# control-17.net
KiCad netlist of a schematic drawn in EAGLE
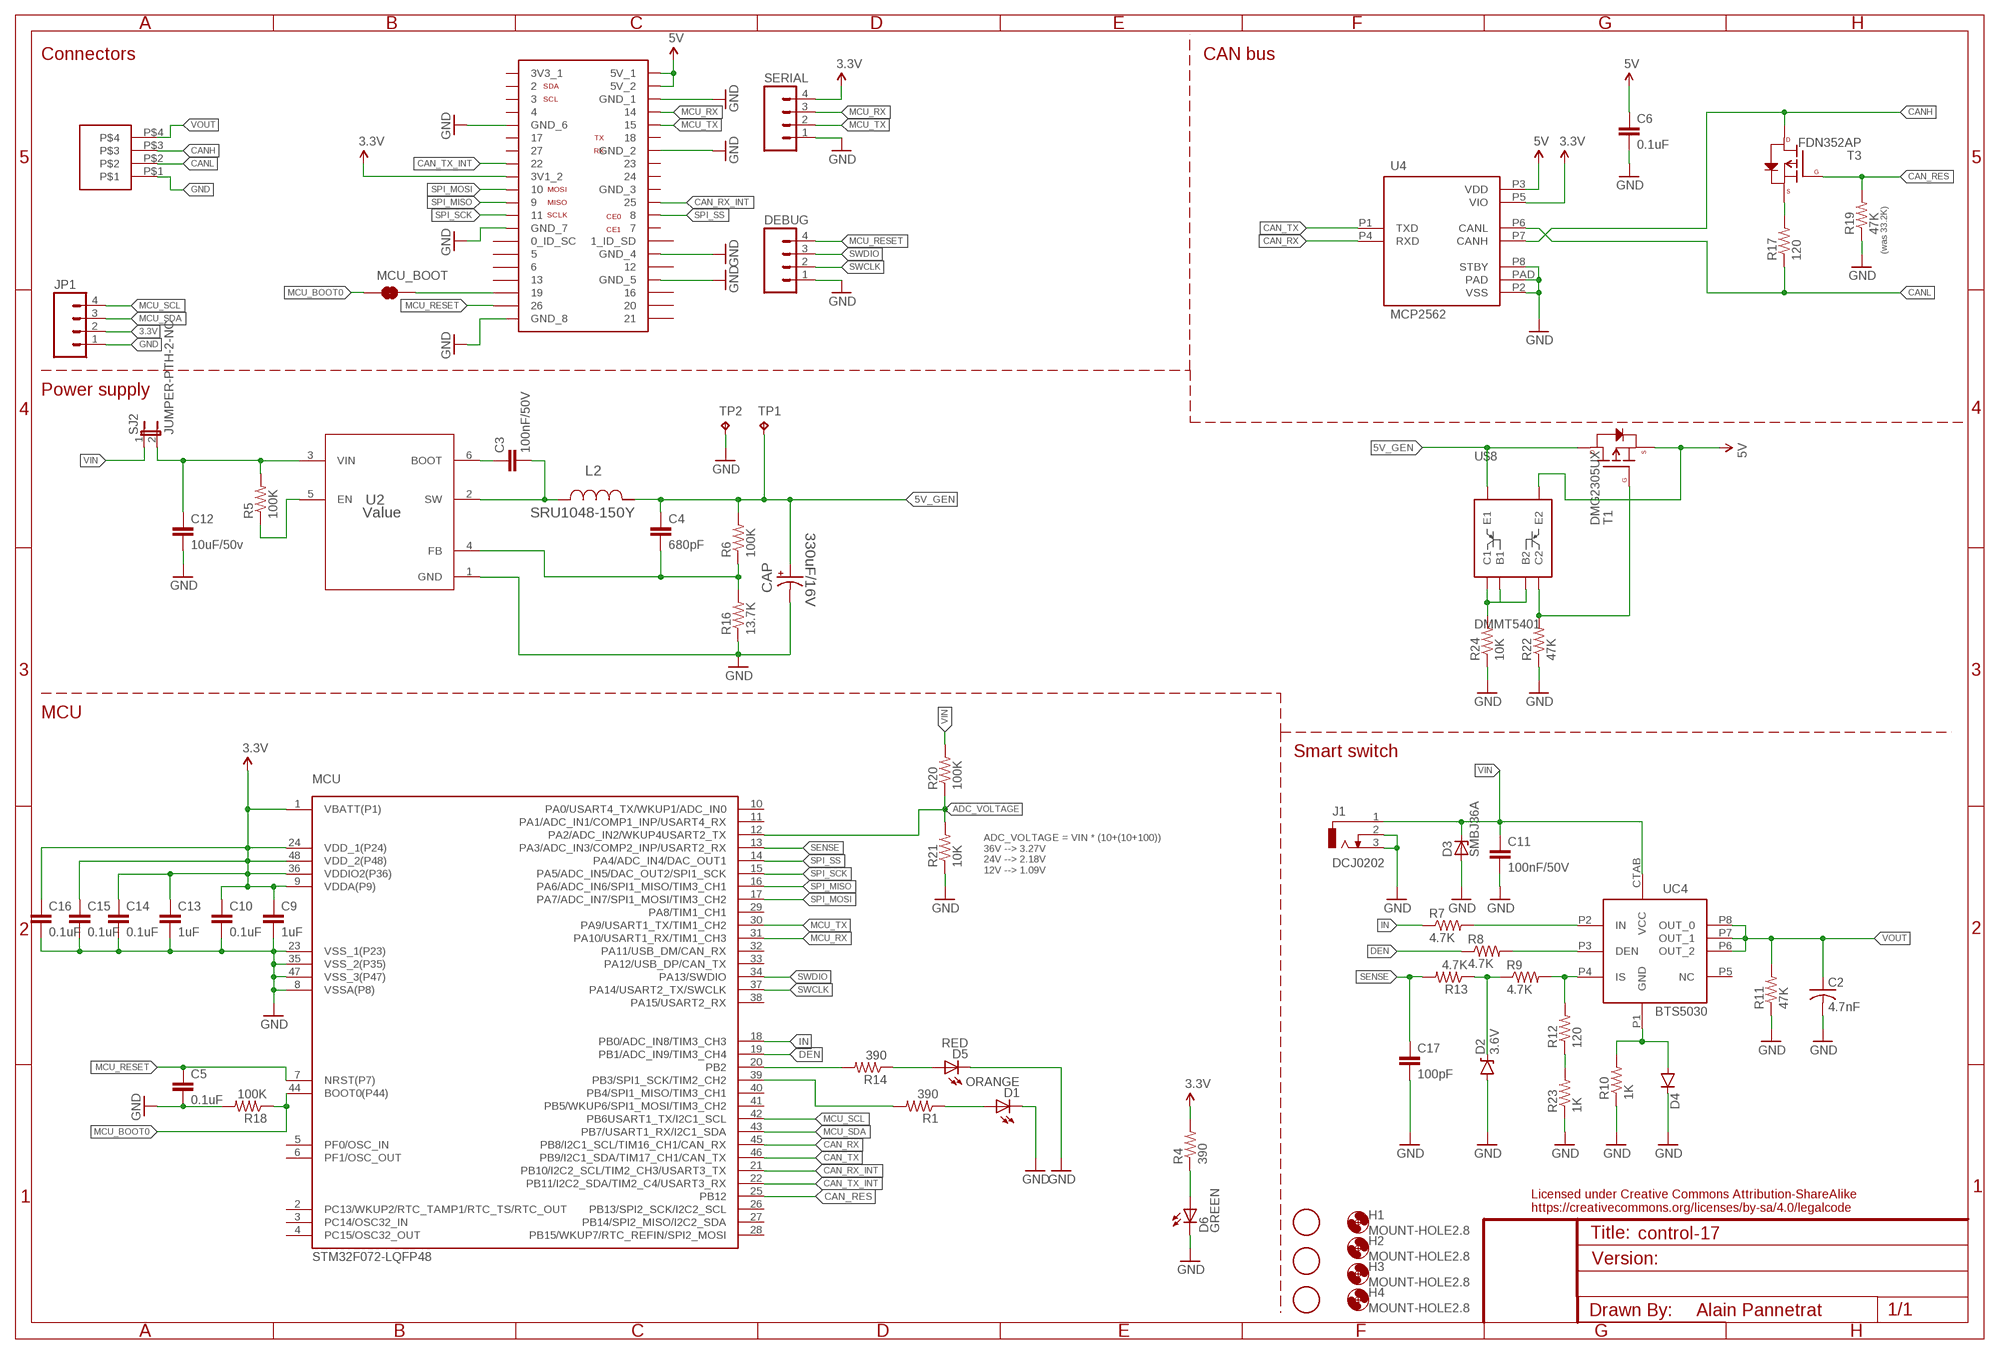
[diagram p0: schematic, sheet 1]

(export (version "E")
  (design (tool "Eeschema 10.0.6"))
  (components
    (comp (ref "C2")
      (value "4.7nF")
      (footprint "eagle-import:C0805")
      (libsource (lib "eagle-import") (part "C-USC0805"))
    )
    (comp (ref "C3")
      (value "100nF/50V")
      (footprint "eagle-import:0805")
      (libsource (lib "eagle-import") (part "CAP0805"))
    )
    (comp (ref "C4")
      (value "680pF")
      (footprint "eagle-import:0603-CAP")
      (libsource (lib "eagle-import") (part "SparkFun-Passives_CAP0603-CAP"))
    )
    (comp (ref "C5")
      (value "0.1uF")
      (footprint "eagle-import:0603-CAP")
      (libsource (lib "eagle-import") (part "CAP0603-CAP"))
    )
    (comp (ref "C6")
      (value "0.1uF")
      (footprint "eagle-import:0603-CAP")
      (libsource (lib "eagle-import") (part "CAP0603-CAP"))
    )
    (comp (ref "C9")
      (value "1uF")
      (footprint "eagle-import:0805")
      (libsource (lib "eagle-import") (part "CAP0805"))
    )
    (comp (ref "C10")
      (value "0.1uF")
      (footprint "eagle-import:0603-CAP")
      (libsource (lib "eagle-import") (part "CAP0603-CAP"))
    )
    (comp (ref "C11")
      (value "100nF/50V")
      (footprint "eagle-import:0805")
      (libsource (lib "eagle-import") (part "CAP0805"))
    )
    (comp (ref "C12")
      (value "10uF/50v")
      (footprint "eagle-import:1206")
      (libsource (lib "eagle-import") (part "CAP1206"))
    )
    (comp (ref "C13")
      (value "1uF")
      (footprint "eagle-import:0805")
      (libsource (lib "eagle-import") (part "CAP0805"))
    )
    (comp (ref "C14")
      (value "0.1uF")
      (footprint "eagle-import:0603-CAP")
      (libsource (lib "eagle-import") (part "CAP0603-CAP"))
    )
    (comp (ref "C15")
      (value "0.1uF")
      (footprint "eagle-import:0603-CAP")
      (libsource (lib "eagle-import") (part "CAP0603-CAP"))
    )
    (comp (ref "C16")
      (value "0.1uF")
      (footprint "eagle-import:0603-CAP")
      (libsource (lib "eagle-import") (part "CAP0603-CAP"))
    )
    (comp (ref "C17")
      (value "100pF")
      (footprint "eagle-import:0805")
      (libsource (lib "eagle-import") (part "CAP0805"))
    )
    (comp (ref "CAP")
      (value "330uF/16V")
      (footprint "eagle-import:PANASONIC_E")
      (libsource (lib "eagle-import") (part "CAP_POLE"))
    )
    (comp (ref "D1")
      (value "ORANGE")
      (footprint "eagle-import:CHIPLED_0805")
      (libsource (lib "eagle-import") (part "LEDCHIPLED_0805"))
    )
    (comp (ref "D2")
      (value "3.6V")
      (footprint "eagle-import:SOD-323")
      (libsource (lib "eagle-import") (part "DIODE-ZENER3.3V"))
    )
    (comp (ref "D3")
      (value "SMBJ36A")
      (footprint "eagle-import:SMB")
      (libsource (lib "eagle-import") (part "ZENER-DIODESMB"))
    )
    (comp (ref "D4")
      (value "DIODESMA")
      (footprint "eagle-import:SMA-DIODE")
      (libsource (lib "eagle-import") (part "DIODESMA"))
    )
    (comp (ref "D5")
      (value "RED")
      (footprint "eagle-import:CHIPLED_0805")
      (libsource (lib "eagle-import") (part "LEDCHIPLED_0805"))
    )
    (comp (ref "D6")
      (value "GREEN")
      (footprint "eagle-import:CHIPLED_0805")
      (libsource (lib "eagle-import") (part "LEDCHIPLED_0805"))
    )
    (comp (ref "DEBUG")
      (value "M04PTH")
      (footprint "eagle-import:1X04")
      (libsource (lib "eagle-import") (part "M04PTH"))
    )
    (comp (ref "H1")
      (value "MOUNT-HOLE2.8")
      (footprint "eagle-import:2,8")
      (libsource (lib "eagle-import") (part "MOUNT-HOLE2.8"))
    )
    (comp (ref "H2")
      (value "MOUNT-HOLE2.8")
      (footprint "eagle-import:2,8")
      (libsource (lib "eagle-import") (part "MOUNT-HOLE2.8"))
    )
    (comp (ref "H3")
      (value "MOUNT-HOLE2.8")
      (footprint "eagle-import:2,8")
      (libsource (lib "eagle-import") (part "MOUNT-HOLE2.8"))
    )
    (comp (ref "H4")
      (value "MOUNT-HOLE2.8")
      (footprint "eagle-import:2,8")
      (libsource (lib "eagle-import") (part "MOUNT-HOLE2.8"))
    )
    (comp (ref "J1")
      (value "DCJ0202")
      (footprint "eagle-import:DCJ0202")
      (libsource (lib "eagle-import") (part "DCJ0202"))
    )
    (comp (ref "JP1")
      (value "M04JST")
      (footprint "eagle-import:1X04-1.5MM_JST")
      (libsource (lib "eagle-import") (part "M04JST"))
    )
    (comp (ref "L2")
      (value "SRU1048-150Y")
      (footprint "eagle-import:SRU1048")
      (fields (field (name "MANUFACTURER_PART_NUMBER") "SRU1048150Y"))
      (libsource (lib "eagle-import") (part "SRU1048-150Y"))
    )
    (comp (ref "MCU")
      (value "STM32F072-LQFP48")
      (footprint "eagle-import:LQFP48")
      (libsource (lib "eagle-import") (part "STM32F072-LQFP48"))
    )
    (comp (ref "MCU_BOOT")
      (value "JUMPER-PAD-2-NC_BY_TRACE")
      (footprint "eagle-import:PAD-JUMPER-2-NC_BY_TRACE_YES_SILK")
      (libsource (lib "eagle-import") (part "JUMPER-PAD-2-NC_BY_TRACE"))
    )
    (comp (ref "PI")
      (value "RASPBERRY-PI-GPIO-SEPARATE")
      (footprint "eagle-import:2X20")
      (libsource (lib "eagle-import") (part "RASPBERRY-PI-GPIO-SEPARATE"))
    )
    (comp (ref "R1")
      (value "390")
      (footprint "eagle-import:R0603")
      (libsource (lib "eagle-import") (part "R-US_R0603"))
    )
    (comp (ref "R4")
      (value "390")
      (footprint "eagle-import:R0603")
      (libsource (lib "eagle-import") (part "R-US_R0603"))
    )
    (comp (ref "R5")
      (value "100K")
      (footprint "eagle-import:R0603")
      (libsource (lib "eagle-import") (part "resistor_R-US_R0603"))
    )
    (comp (ref "R6")
      (value "100K")
      (footprint "eagle-import:R0603")
      (libsource (lib "eagle-import") (part "resistor_R-US_R0603"))
    )
    (comp (ref "R7")
      (value "4.7K")
      (footprint "eagle-import:R0805")
      (libsource (lib "eagle-import") (part "resistor_R-US_R0805"))
    )
    (comp (ref "R8")
      (value "4.7K")
      (footprint "eagle-import:R0805")
      (libsource (lib "eagle-import") (part "resistor_R-US_R0805"))
    )
    (comp (ref "R9")
      (value "4.7K")
      (footprint "eagle-import:R0805")
      (libsource (lib "eagle-import") (part "resistor_R-US_R0805"))
    )
    (comp (ref "R10")
      (value "1K")
      (footprint "eagle-import:R0805")
      (libsource (lib "eagle-import") (part "resistor_R-US_R0805"))
    )
    (comp (ref "R11")
      (value "47K")
      (footprint "eagle-import:R0805")
      (libsource (lib "eagle-import") (part "R-US_R0805"))
    )
    (comp (ref "R12")
      (value "120")
      (footprint "eagle-import:R0805")
      (libsource (lib "eagle-import") (part "resistor_R-US_R0805"))
    )
    (comp (ref "R13")
      (value "4.7K")
      (footprint "eagle-import:R0805")
      (libsource (lib "eagle-import") (part "resistor_R-US_R0805"))
    )
    (comp (ref "R14")
      (value "390")
      (footprint "eagle-import:R0603")
      (libsource (lib "eagle-import") (part "R-US_R0603"))
    )
    (comp (ref "R16")
      (value "13.7K")
      (footprint "eagle-import:R0805")
      (libsource (lib "eagle-import") (part "R-US_R0805"))
    )
    (comp (ref "R17")
      (value "120")
      (footprint "eagle-import:R0805")
      (libsource (lib "eagle-import") (part "resistor_R-US_R0805"))
    )
    (comp (ref "R18")
      (value "100K")
      (footprint "eagle-import:R0603")
      (libsource (lib "eagle-import") (part "R-US_R0603"))
    )
    (comp (ref "R19")
      (value "47K")
      (footprint "eagle-import:R0805")
      (libsource (lib "eagle-import") (part "R-US_R0805"))
    )
    (comp (ref "R20")
      (value "100K")
      (footprint "eagle-import:R0603")
      (libsource (lib "eagle-import") (part "resistor_R-US_R0603"))
    )
    (comp (ref "R21")
      (value "10K")
      (footprint "eagle-import:R0805")
      (libsource (lib "eagle-import") (part "resistor_R-US_R0805"))
    )
    (comp (ref "R22")
      (value "47K")
      (footprint "eagle-import:R0805")
      (libsource (lib "eagle-import") (part "resistor_R-US_R0805"))
    )
    (comp (ref "R23")
      (value "1K")
      (footprint "eagle-import:R0805")
      (libsource (lib "eagle-import") (part "resistor_R-US_R0805"))
    )
    (comp (ref "R24")
      (value "10K")
      (footprint "eagle-import:R0805")
      (libsource (lib "eagle-import") (part "resistor_R-US_R0805"))
    )
    (comp (ref "SERIAL")
      (value "M04PTH")
      (footprint "eagle-import:1X04")
      (libsource (lib "eagle-import") (part "M04PTH"))
    )
    (comp (ref "SJ2")
      (value "JUMPER-PTH-2-NC")
      (footprint "eagle-import:PTH-JUMPER-NC_BOTTOM_NO_SILK")
      (libsource (lib "eagle-import") (part "JUMPER-PTH-2-NC"))
    )
    (comp (ref "T1")
      (value "DMG2305UX")
      (footprint "eagle-import:SOT23-3")
      (libsource (lib "eagle-import") (part "P-CHANNEL-MOSFET"))
    )
    (comp (ref "T3")
      (value "FDN352AP")
      (footprint "eagle-import:SOT23-3")
      (libsource (lib "eagle-import") (part "P-CHANNEL-MOSFET"))
    )
    (comp (ref "TP1")
      (value "TPPAD1-13")
      (footprint "eagle-import:P1-13")
      (libsource (lib "eagle-import") (part "TPPAD1-13"))
    )
    (comp (ref "TP2")
      (value "TPPAD1-13")
      (footprint "eagle-import:P1-13")
      (libsource (lib "eagle-import") (part "TPPAD1-13"))
    )
    (comp (ref "U$3")
      (value "M04-PLUG-3.5")
      (footprint "eagle-import:M04-PLUG-3.5")
      (libsource (lib "eagle-import") (part "M04-PLUG-3.5"))
    )
    (comp (ref "U$4")
      (value "FIDUCIAL")
      (footprint "eagle-import:FIDUCIAL_1MM")
      (libsource (lib "eagle-import") (part "FIDUCIAL"))
    )
    (comp (ref "U$5")
      (value "FIDUCIAL")
      (footprint "eagle-import:FIDUCIAL_1MM")
      (libsource (lib "eagle-import") (part "FIDUCIAL"))
    )
    (comp (ref "U$6")
      (value "FIDUCIAL")
      (footprint "eagle-import:FIDUCIAL_1MM")
      (libsource (lib "eagle-import") (part "FIDUCIAL"))
    )
    (comp (ref "U$8")
      (value "DMMT5401")
      (footprint "eagle-import:SOT-23-6")
      (libsource (lib "eagle-import") (part "DMMT5401"))
    )
    (comp (ref "U2")
      (value "Value")
      (footprint "eagle-import:DDC0006A_N")
      (fields
        (field (name "ALTERNATEPARTNUMBER") "TPS54202DDCT")
        (field (name "MANUFACTURER") "Texas Instruments")
        (field (name "MANUFACTURER_PART_NUMBER") "TPS54202DDCR")
      )
      (libsource (lib "eagle-import") (part "TPS54202DDCR"))
    )
    (comp (ref "U4")
      (value "MCP2562")
      (footprint "eagle-import:DFN3X3")
      (libsource (lib "eagle-import") (part "MCP2562"))
    )
    (comp (ref "UC4")
      (value "BTS5030")
      (footprint "eagle-import:PG-DSO-8-43")
      (libsource (lib "eagle-import") (part "BTS5030"))
    )
  )
  (nets
    (net (code "1") (name "/3V3_1") (class "Default")
      (node (ref "PI") (pin "1") (pinfunction "3V3_1_1") (pintype "power_in"))
    )
    (net (code "2") (name "3.3V") (class "Default")
      (node (ref "C10") (pin "1") (pinfunction "1_1") (pintype "passive"))
      (node (ref "C13") (pin "1") (pinfunction "1_1") (pintype "passive"))
      (node (ref "C14") (pin "1") (pinfunction "1_1") (pintype "passive"))
      (node (ref "C15") (pin "1") (pinfunction "1_1") (pintype "passive"))
      (node (ref "C16") (pin "1") (pinfunction "1_1") (pintype "passive"))
      (node (ref "C9") (pin "1") (pinfunction "1_1") (pintype "passive"))
      (node (ref "JP1") (pin "2") (pinfunction "2_2") (pintype "passive"))
      (node (ref "MCU") (pin "1") (pinfunction "VBATT(P1)_1") (pintype "bidirectional"))
      (node (ref "MCU") (pin "24") (pinfunction "VDD_1(P24)_24") (pintype "bidirectional"))
      (node (ref "MCU") (pin "36") (pinfunction "VDDIO2(P36)_36") (pintype "bidirectional"))
      (node (ref "MCU") (pin "48") (pinfunction "VDD_2(P48)_48") (pintype "bidirectional"))
      (node (ref "MCU") (pin "9") (pinfunction "VDDA(P9)_9") (pintype "bidirectional"))
      (node (ref "PI") (pin "17") (pinfunction "3V1_2_17") (pintype "power_in"))
      (node (ref "R4") (pin "2") (pinfunction "2_2") (pintype "passive"))
      (node (ref "SERIAL") (pin "4") (pinfunction "4_4") (pintype "passive"))
      (node (ref "U4") (pin "P5") (pinfunction "VIO_P5") (pintype "bidirectional"))
    )
    (net (code "3") (name "5V") (class "Default")
      (node (ref "C6") (pin "1") (pinfunction "1_1") (pintype "passive"))
      (node (ref "PI") (pin "2") (pinfunction "5V_1_2") (pintype "power_in"))
      (node (ref "PI") (pin "4") (pinfunction "5V_2_4") (pintype "power_in"))
      (node (ref "T1") (pin "2") (pinfunction "S_2") (pintype "passive"))
      (node (ref "U$8") (pin "5") (pinfunction "E2_5") (pintype "bidirectional"))
      (node (ref "U4") (pin "P3") (pinfunction "VDD_P3") (pintype "bidirectional"))
    )
    (net (code "4") (name "5V_GEN") (class "Default")
      (node (ref "C4") (pin "1") (pinfunction "1_1") (pintype "passive"))
      (node (ref "CAP") (pin "+") (pinfunction "+_+") (pintype "passive"))
      (node (ref "L2") (pin "2") (pinfunction "2_2") (pintype "passive"))
      (node (ref "R6") (pin "2") (pinfunction "2_2") (pintype "passive"))
      (node (ref "T1") (pin "3") (pinfunction "D_3") (pintype "passive"))
      (node (ref "TP1") (pin "TP") (pinfunction "TP_TP") (pintype "input"))
      (node (ref "U$8") (pin "6") (pinfunction "E1_6") (pintype "bidirectional"))
    )
    (net (code "5") (name "ADC_VOLTAGE") (class "Default")
      (node (ref "MCU") (pin "12") (pinfunction "PA2/ADC_IN2/WKUP4USART2_TX_12") (pintype "bidirectional"))
      (node (ref "R20") (pin "1") (pinfunction "1_1") (pintype "passive"))
      (node (ref "R21") (pin "2") (pinfunction "2_2") (pintype "passive"))
    )
    (net (code "6") (name "CANH") (class "Default")
      (node (ref "T3") (pin "3") (pinfunction "D_3") (pintype "passive"))
      (node (ref "U$3") (pin "P$3") (pinfunction "P$3_P$3") (pintype "bidirectional"))
      (node (ref "U4") (pin "P7") (pinfunction "CANH_P7") (pintype "bidirectional"))
    )
    (net (code "7") (name "CANL") (class "Default")
      (node (ref "R17") (pin "1") (pinfunction "1_1") (pintype "passive"))
      (node (ref "U$3") (pin "P$2") (pinfunction "P$2_P$2") (pintype "bidirectional"))
      (node (ref "U4") (pin "P6") (pinfunction "CANL_P6") (pintype "bidirectional"))
    )
    (net (code "8") (name "CAN_RES") (class "Default")
      (node (ref "MCU") (pin "25") (pinfunction "PB12_25") (pintype "bidirectional"))
      (node (ref "R19") (pin "2") (pinfunction "2_2") (pintype "passive"))
      (node (ref "T3") (pin "1") (pinfunction "G_1") (pintype "passive"))
    )
    (net (code "9") (name "CAN_RX") (class "Default")
      (node (ref "MCU") (pin "45") (pinfunction "PB8/I2C1_SCL/TIM16_CH1/CAN_RX_45") (pintype "bidirectional"))
      (node (ref "U4") (pin "P4") (pinfunction "RXD_P4") (pintype "bidirectional"))
    )
    (net (code "10") (name "CAN_RX_INT") (class "Default")
      (node (ref "MCU") (pin "21") (pinfunction "PB10/I2C2_SCL/TIM2_CH3/USART3_TX_21") (pintype "bidirectional"))
      (node (ref "PI") (pin "22") (pinfunction "25_22") (pintype "bidirectional"))
    )
    (net (code "11") (name "CAN_TX") (class "Default")
      (node (ref "MCU") (pin "46") (pinfunction "PB9/I2C1_SDA/TIM17_CH1/CAN_TX_46") (pintype "bidirectional"))
      (node (ref "U4") (pin "P1") (pinfunction "TXD_P1") (pintype "bidirectional"))
    )
    (net (code "12") (name "CAN_TX_INT") (class "Default")
      (node (ref "MCU") (pin "22") (pinfunction "PB11/I2C2_SDA/TIM2_C4/USART3_RX_22") (pintype "bidirectional"))
      (node (ref "PI") (pin "15") (pinfunction "22_15") (pintype "bidirectional"))
    )
    (net (code "13") (name "DEN") (class "Default")
      (node (ref "MCU") (pin "19") (pinfunction "PB1/ADC_IN9/TIM3_CH4_19") (pintype "bidirectional"))
      (node (ref "R8") (pin "1") (pinfunction "1_1") (pintype "passive"))
    )
    (net (code "14") (name "GND") (class "Default")
      (node (ref "C10") (pin "2") (pinfunction "2_2") (pintype "passive"))
      (node (ref "C11") (pin "2") (pinfunction "2_2") (pintype "passive"))
      (node (ref "C12") (pin "2") (pinfunction "2_2") (pintype "passive"))
      (node (ref "C13") (pin "2") (pinfunction "2_2") (pintype "passive"))
      (node (ref "C14") (pin "2") (pinfunction "2_2") (pintype "passive"))
      (node (ref "C15") (pin "2") (pinfunction "2_2") (pintype "passive"))
      (node (ref "C16") (pin "2") (pinfunction "2_2") (pintype "passive"))
      (node (ref "C17") (pin "2") (pinfunction "2_2") (pintype "passive"))
      (node (ref "C2") (pin "2") (pinfunction "2_2") (pintype "passive"))
      (node (ref "C5") (pin "2") (pinfunction "2_2") (pintype "passive"))
      (node (ref "C6") (pin "2") (pinfunction "2_2") (pintype "passive"))
      (node (ref "C9") (pin "2") (pinfunction "2_2") (pintype "passive"))
      (node (ref "CAP") (pin "-") (pinfunction "-_-") (pintype "passive"))
      (node (ref "D1") (pin "C") (pinfunction "C_C") (pintype "passive"))
      (node (ref "D2") (pin "A") (pinfunction "A_A") (pintype "passive"))
      (node (ref "D3") (pin "A") (pinfunction "A_A") (pintype "passive"))
      (node (ref "D4") (pin "C") (pinfunction "C_C") (pintype "passive"))
      (node (ref "D5") (pin "C") (pinfunction "C_C") (pintype "passive"))
      (node (ref "D6") (pin "C") (pinfunction "C_C") (pintype "passive"))
      (node (ref "DEBUG") (pin "1") (pinfunction "1_1") (pintype "passive"))
      (node (ref "J1") (pin "2") (pinfunction "2_2") (pintype "passive"))
      (node (ref "J1") (pin "3") (pinfunction "3_3") (pintype "passive"))
      (node (ref "JP1") (pin "1") (pinfunction "1_1") (pintype "passive"))
      (node (ref "MCU") (pin "23") (pinfunction "VSS_1(P23)_23") (pintype "bidirectional"))
      (node (ref "MCU") (pin "35") (pinfunction "VSS_2(P35)_35") (pintype "bidirectional"))
      (node (ref "MCU") (pin "47") (pinfunction "VSS_3(P47)_47") (pintype "bidirectional"))
      (node (ref "MCU") (pin "8") (pinfunction "VSSA(P8)_8") (pintype "bidirectional"))
      (node (ref "PI") (pin "14") (pinfunction "GND_2_14") (pintype "passive"))
      (node (ref "PI") (pin "25") (pinfunction "GND_7_25") (pintype "passive"))
      (node (ref "PI") (pin "30") (pinfunction "GND_4_30") (pintype "passive"))
      (node (ref "PI") (pin "34") (pinfunction "GND_5_34") (pintype "passive"))
      (node (ref "PI") (pin "39") (pinfunction "GND_8_39") (pintype "passive"))
      (node (ref "PI") (pin "6") (pinfunction "GND_1_6") (pintype "passive"))
      (node (ref "PI") (pin "9") (pinfunction "GND_6_9") (pintype "passive"))
      (node (ref "R10") (pin "1") (pinfunction "1_1") (pintype "passive"))
      (node (ref "R11") (pin "1") (pinfunction "1_1") (pintype "passive"))
      (node (ref "R16") (pin "1") (pinfunction "1_1") (pintype "passive"))
      (node (ref "R18") (pin "2") (pinfunction "2_2") (pintype "passive"))
      (node (ref "R19") (pin "1") (pinfunction "1_1") (pintype "passive"))
      (node (ref "R21") (pin "1") (pinfunction "1_1") (pintype "passive"))
      (node (ref "R22") (pin "1") (pinfunction "1_1") (pintype "passive"))
      (node (ref "R23") (pin "1") (pinfunction "1_1") (pintype "passive"))
      (node (ref "R24") (pin "1") (pinfunction "1_1") (pintype "passive"))
      (node (ref "SERIAL") (pin "1") (pinfunction "1_1") (pintype "passive"))
      (node (ref "TP2") (pin "TP") (pinfunction "TP_TP") (pintype "input"))
      (node (ref "U$3") (pin "P$1") (pinfunction "P$1_P$1") (pintype "bidirectional"))
      (node (ref "U2") (pin "1") (pinfunction "GND_1") (pintype "power_in"))
      (node (ref "U4") (pin "P2") (pinfunction "VSS_P2") (pintype "bidirectional"))
      (node (ref "U4") (pin "P8") (pinfunction "STBY_P8") (pintype "bidirectional"))
      (node (ref "U4") (pin "PAD") (pinfunction "PAD_PAD") (pintype "bidirectional"))
    )
    (net (code "15") (name "IN") (class "Default")
      (node (ref "MCU") (pin "18") (pinfunction "PB0/ADC_IN8/TIM3_CH3_18") (pintype "bidirectional"))
      (node (ref "R7") (pin "1") (pinfunction "1_1") (pintype "passive"))
    )
    (net (code "16") (name "MCU_BOOT0") (class "Default")
      (node (ref "MCU") (pin "44") (pinfunction "BOOT0(P44)_44") (pintype "bidirectional"))
      (node (ref "MCU_BOOT") (pin "1") (pinfunction "1_1") (pintype "passive"))
      (node (ref "R18") (pin "1") (pinfunction "1_1") (pintype "passive"))
    )
    (net (code "17") (name "MCU_RESET") (class "Default")
      (node (ref "C5") (pin "1") (pinfunction "1_1") (pintype "passive"))
      (node (ref "DEBUG") (pin "4") (pinfunction "4_4") (pintype "passive"))
      (node (ref "MCU") (pin "7") (pinfunction "NRST(P7)_7") (pintype "bidirectional"))
      (node (ref "PI") (pin "37") (pinfunction "26_37") (pintype "bidirectional"))
    )
    (net (code "18") (name "MCU_RX") (class "Default")
      (node (ref "MCU") (pin "31") (pinfunction "PA10/USART1_RX/TIM1_CH3_31") (pintype "bidirectional"))
      (node (ref "PI") (pin "8") (pinfunction "14_8") (pintype "bidirectional"))
      (node (ref "SERIAL") (pin "3") (pinfunction "3_3") (pintype "passive"))
    )
    (net (code "19") (name "MCU_SCL") (class "Default")
      (node (ref "JP1") (pin "4") (pinfunction "4_4") (pintype "passive"))
      (node (ref "MCU") (pin "42") (pinfunction "PB6USART1_TX/I2C1_SCL_42") (pintype "bidirectional"))
    )
    (net (code "20") (name "MCU_SDA") (class "Default")
      (node (ref "JP1") (pin "3") (pinfunction "3_3") (pintype "passive"))
      (node (ref "MCU") (pin "43") (pinfunction "PB7/USART1_RX/I2C1_SDA_43") (pintype "bidirectional"))
    )
    (net (code "21") (name "MCU_TX") (class "Default")
      (node (ref "MCU") (pin "30") (pinfunction "PA9/USART1_TX/TIM1_CH2_30") (pintype "bidirectional"))
      (node (ref "PI") (pin "10") (pinfunction "15_10") (pintype "bidirectional"))
      (node (ref "SERIAL") (pin "2") (pinfunction "2_2") (pintype "passive"))
    )
    (net (code "22") (name "Net-(D1-PadA)") (class "Default")
      (node (ref "D1") (pin "A") (pinfunction "A_A") (pintype "passive"))
      (node (ref "R1") (pin "1") (pinfunction "1_1") (pintype "passive"))
    )
    (net (code "23") (name "Net-(D2-PadC)") (class "Default")
      (node (ref "D2") (pin "C") (pinfunction "C_C") (pintype "passive"))
      (node (ref "R13") (pin "1") (pinfunction "1_1") (pintype "passive"))
      (node (ref "R9") (pin "1") (pinfunction "1_1") (pintype "passive"))
    )
    (net (code "24") (name "Net-(D5-PadA)") (class "Default")
      (node (ref "D5") (pin "A") (pinfunction "A_A") (pintype "passive"))
      (node (ref "R14") (pin "1") (pinfunction "1_1") (pintype "passive"))
    )
    (net (code "25") (name "Net-(D6-PadA)") (class "Default")
      (node (ref "D6") (pin "A") (pinfunction "A_A") (pintype "passive"))
      (node (ref "R4") (pin "1") (pinfunction "1_1") (pintype "passive"))
    )
    (net (code "26") (name "Net-(MCU-PB2)") (class "Default")
      (node (ref "MCU") (pin "20") (pinfunction "PB2_20") (pintype "bidirectional"))
      (node (ref "R14") (pin "2") (pinfunction "2_2") (pintype "passive"))
    )
    (net (code "27") (name "Net-(MCU-PB3{slash}SPI1_SCK{slash}TIM2_CH2)") (class "Default")
      (node (ref "MCU") (pin "39") (pinfunction "PB3/SPI1_SCK/TIM2_CH2_39") (pintype "bidirectional"))
      (node (ref "R1") (pin "2") (pinfunction "2_2") (pintype "passive"))
    )
    (net (code "28") (name "Net-(PI-19)") (class "Default")
      (node (ref "MCU_BOOT") (pin "2") (pinfunction "2_2") (pintype "passive"))
      (node (ref "PI") (pin "35") (pinfunction "19_35") (pintype "bidirectional"))
    )
    (net (code "29") (name "Net-(R12-Pad1)") (class "Default")
      (node (ref "R12") (pin "1") (pinfunction "1_1") (pintype "passive"))
      (node (ref "R23") (pin "2") (pinfunction "2_2") (pintype "passive"))
    )
    (net (code "30") (name "Net-(T1-G)") (class "Default")
      (node (ref "R22") (pin "2") (pinfunction "2_2") (pintype "passive"))
      (node (ref "T1") (pin "1") (pinfunction "G_1") (pintype "passive"))
      (node (ref "U$8") (pin "4") (pinfunction "C2_4") (pintype "bidirectional"))
    )
    (net (code "31") (name "Net-(T3-S)") (class "Default")
      (node (ref "R17") (pin "2") (pinfunction "2_2") (pintype "passive"))
      (node (ref "T3") (pin "2") (pinfunction "S_2") (pintype "passive"))
    )
    (net (code "32") (name "Net-(U$8-B1)") (class "Default")
      (node (ref "R24") (pin "2") (pinfunction "2_2") (pintype "passive"))
      (node (ref "U$8") (pin "1") (pinfunction "C1_1") (pintype "bidirectional"))
      (node (ref "U$8") (pin "2") (pinfunction "B1_2") (pintype "bidirectional"))
      (node (ref "U$8") (pin "3") (pinfunction "B2_3") (pintype "bidirectional"))
    )
    (net (code "33") (name "Net-(U2-BOOT)") (class "Default")
      (node (ref "C3") (pin "1") (pinfunction "1_1") (pintype "passive"))
      (node (ref "U2") (pin "6") (pinfunction "BOOT_6") (pintype "power_in"))
    )
    (net (code "34") (name "Net-(U2-EN)") (class "Default")
      (node (ref "R5") (pin "1") (pinfunction "1_1") (pintype "passive"))
      (node (ref "U2") (pin "5") (pinfunction "EN_5") (pintype "input"))
    )
    (net (code "35") (name "Net-(U2-FB)") (class "Default")
      (node (ref "C4") (pin "2") (pinfunction "2_2") (pintype "passive"))
      (node (ref "R16") (pin "2") (pinfunction "2_2") (pintype "passive"))
      (node (ref "R6") (pin "1") (pinfunction "1_1") (pintype "passive"))
      (node (ref "U2") (pin "4") (pinfunction "FB_4") (pintype "input"))
    )
    (net (code "36") (name "Net-(U2-SW)") (class "Default")
      (node (ref "C3") (pin "2") (pinfunction "2_2") (pintype "passive"))
      (node (ref "L2") (pin "1") (pinfunction "1_1") (pintype "passive"))
      (node (ref "U2") (pin "2") (pinfunction "SW_2") (pintype "power_in"))
    )
    (net (code "37") (name "Net-(U2-VIN)") (class "Default")
      (node (ref "C12") (pin "1") (pinfunction "1_1") (pintype "passive"))
      (node (ref "R5") (pin "2") (pinfunction "2_2") (pintype "passive"))
      (node (ref "SJ2") (pin "2") (pinfunction "2_2") (pintype "passive"))
      (node (ref "U2") (pin "3") (pinfunction "VIN_3") (pintype "power_in"))
    )
    (net (code "38") (name "Net-(UC4-DEN)") (class "Default")
      (node (ref "R8") (pin "2") (pinfunction "2_2") (pintype "passive"))
      (node (ref "UC4") (pin "P3") (pinfunction "DEN_P3") (pintype "bidirectional"))
    )
    (net (code "39") (name "Net-(UC4-GND)") (class "Default")
      (node (ref "D4") (pin "A") (pinfunction "A_A") (pintype "passive"))
      (node (ref "R10") (pin "2") (pinfunction "2_2") (pintype "passive"))
      (node (ref "UC4") (pin "P1") (pinfunction "GND_P1") (pintype "bidirectional"))
    )
    (net (code "40") (name "Net-(UC4-IN)") (class "Default")
      (node (ref "R7") (pin "2") (pinfunction "2_2") (pintype "passive"))
      (node (ref "UC4") (pin "P2") (pinfunction "IN_P2") (pintype "bidirectional"))
    )
    (net (code "41") (name "Net-(UC4-IS)") (class "Default")
      (node (ref "R12") (pin "2") (pinfunction "2_2") (pintype "passive"))
      (node (ref "R9") (pin "2") (pinfunction "2_2") (pintype "passive"))
      (node (ref "UC4") (pin "P4") (pinfunction "IS_P4") (pintype "bidirectional"))
    )
    (net (code "42") (name "SENSE") (class "Default")
      (node (ref "C17") (pin "1") (pinfunction "1_1") (pintype "passive"))
      (node (ref "MCU") (pin "13") (pinfunction "PA3/ADC_IN3/COMP2_INP/USART2_RX_13") (pintype "bidirectional"))
      (node (ref "R13") (pin "2") (pinfunction "2_2") (pintype "passive"))
    )
    (net (code "43") (name "SPI_MISO") (class "Default")
      (node (ref "MCU") (pin "16") (pinfunction "PA6/ADC_IN6/SPI1_MISO/TIM3_CH1_16") (pintype "bidirectional"))
      (node (ref "PI") (pin "21") (pinfunction "9_21") (pintype "bidirectional"))
    )
    (net (code "44") (name "SPI_MOSI") (class "Default")
      (node (ref "MCU") (pin "17") (pinfunction "PA7/ADC_IN7/SPI1_MOSI/TIM3_CH2_17") (pintype "bidirectional"))
      (node (ref "PI") (pin "19") (pinfunction "10_19") (pintype "bidirectional"))
    )
    (net (code "45") (name "SPI_SCK") (class "Default")
      (node (ref "MCU") (pin "15") (pinfunction "PA5/ADC_IN5/DAC_OUT2/SPI1_SCK_15") (pintype "bidirectional"))
      (node (ref "PI") (pin "23") (pinfunction "11_23") (pintype "bidirectional"))
    )
    (net (code "46") (name "SPI_SS") (class "Default")
      (node (ref "MCU") (pin "14") (pinfunction "PA4/ADC_IN4/DAC_OUT1_14") (pintype "bidirectional"))
      (node (ref "PI") (pin "24") (pinfunction "8_24") (pintype "bidirectional"))
    )
    (net (code "47") (name "SWCLK") (class "Default")
      (node (ref "DEBUG") (pin "2") (pinfunction "2_2") (pintype "passive"))
      (node (ref "MCU") (pin "37") (pinfunction "PA14/USART2_TX/SWCLK_37") (pintype "bidirectional"))
    )
    (net (code "48") (name "SWDIO") (class "Default")
      (node (ref "DEBUG") (pin "3") (pinfunction "3_3") (pintype "passive"))
      (node (ref "MCU") (pin "34") (pinfunction "PA13/SWDIO_34") (pintype "bidirectional"))
    )
    (net (code "49") (name "VIN") (class "Default")
      (node (ref "C11") (pin "1") (pinfunction "1_1") (pintype "passive"))
      (node (ref "D3") (pin "C") (pinfunction "C_C") (pintype "passive"))
      (node (ref "J1") (pin "1") (pinfunction "1_1") (pintype "passive"))
      (node (ref "R20") (pin "2") (pinfunction "2_2") (pintype "passive"))
      (node (ref "SJ2") (pin "1") (pinfunction "1_1") (pintype "passive"))
      (node (ref "UC4") (pin "CTAB") (pinfunction "VCC_CTAB") (pintype "bidirectional"))
    )
    (net (code "50") (name "VOUT") (class "Default")
      (node (ref "C2") (pin "1") (pinfunction "1_1") (pintype "passive"))
      (node (ref "R11") (pin "2") (pinfunction "2_2") (pintype "passive"))
      (node (ref "U$3") (pin "P$4") (pinfunction "P$4_P$4") (pintype "bidirectional"))
      (node (ref "UC4") (pin "P6") (pinfunction "OUT_2_P6") (pintype "bidirectional"))
      (node (ref "UC4") (pin "P7") (pinfunction "OUT_1_P7") (pintype "bidirectional"))
      (node (ref "UC4") (pin "P8") (pinfunction "OUT_0_P8") (pintype "bidirectional"))
    )
    (net (code "51") (name "unconnected-(MCU-PA0{slash}USART4_TX{slash}WKUP1{slash}ADC_IN0-Pad10)") (class "Default")
      (node (ref "MCU") (pin "10") (pinfunction "PA0/USART4_TX/WKUP1/ADC_IN0_10") (pintype "bidirectional"))
    )
    (net (code "52") (name "unconnected-(MCU-PA1{slash}ADC_IN1{slash}COMP1_INP{slash}USART4_RX-Pad11)") (class "Default")
      (node (ref "MCU") (pin "11") (pinfunction "PA1/ADC_IN1/COMP1_INP/USART4_RX_11") (pintype "bidirectional"))
    )
    (net (code "53") (name "unconnected-(MCU-PA8{slash}TIM1_CH1-Pad29)") (class "Default")
      (node (ref "MCU") (pin "29") (pinfunction "PA8/TIM1_CH1_29") (pintype "bidirectional"))
    )
    (net (code "54") (name "unconnected-(MCU-PA11{slash}USB_DM{slash}CAN_RX-Pad32)") (class "Default")
      (node (ref "MCU") (pin "32") (pinfunction "PA11/USB_DM/CAN_RX_32") (pintype "bidirectional"))
    )
    (net (code "55") (name "unconnected-(MCU-PA12{slash}USB_DP{slash}CAN_TX-Pad33)") (class "Default")
      (node (ref "MCU") (pin "33") (pinfunction "PA12/USB_DP/CAN_TX_33") (pintype "bidirectional"))
    )
    (net (code "56") (name "unconnected-(MCU-PA15{slash}USART2_RX-Pad38)") (class "Default")
      (node (ref "MCU") (pin "38") (pinfunction "PA15/USART2_RX_38") (pintype "bidirectional"))
    )
    (net (code "57") (name "unconnected-(MCU-PB4{slash}SPI1_MISO{slash}TIM3_CH1-Pad40)") (class "Default")
      (node (ref "MCU") (pin "40") (pinfunction "PB4/SPI1_MISO/TIM3_CH1_40") (pintype "bidirectional"))
    )
    (net (code "58") (name "unconnected-(MCU-PB5{slash}WKUP6{slash}SPI1_MOSI{slash}TIM3_CH2-Pad41)") (class "Default")
      (node (ref "MCU") (pin "41") (pinfunction "PB5/WKUP6/SPI1_MOSI/TIM3_CH2_41") (pintype "bidirectional"))
    )
    (net (code "59") (name "unconnected-(MCU-PB13{slash}SPI2_SCK{slash}I2C2_SCL-Pad26)") (class "Default")
      (node (ref "MCU") (pin "26") (pinfunction "PB13/SPI2_SCK/I2C2_SCL_26") (pintype "bidirectional"))
    )
    (net (code "60") (name "unconnected-(MCU-PB14{slash}SPI2_MISO{slash}I2C2_SDA-Pad27)") (class "Default")
      (node (ref "MCU") (pin "27") (pinfunction "PB14/SPI2_MISO/I2C2_SDA_27") (pintype "bidirectional"))
    )
    (net (code "61") (name "unconnected-(MCU-PB15{slash}WKUP7{slash}RTC_REFIN{slash}SPI2_MOSI-Pad28)") (class "Default")
      (node (ref "MCU") (pin "28") (pinfunction "PB15/WKUP7/RTC_REFIN/SPI2_MOSI_28") (pintype "bidirectional"))
    )
    (net (code "62") (name "unconnected-(MCU-PC13{slash}WKUP2{slash}RTC_TAMP1{slash}RTC_TS{slash}RTC_OUT-Pad2)") (class "Default")
      (node (ref "MCU") (pin "2") (pinfunction "PC13/WKUP2/RTC_TAMP1/RTC_TS/RTC_OUT_2") (pintype "bidirectional"))
    )
    (net (code "63") (name "unconnected-(MCU-PC14{slash}OSC32_IN-Pad3)") (class "Default")
      (node (ref "MCU") (pin "3") (pinfunction "PC14/OSC32_IN_3") (pintype "bidirectional"))
    )
    (net (code "64") (name "unconnected-(MCU-PC15{slash}OSC32_OUT-Pad4)") (class "Default")
      (node (ref "MCU") (pin "4") (pinfunction "PC15/OSC32_OUT_4") (pintype "bidirectional"))
    )
    (net (code "65") (name "unconnected-(MCU-PF0{slash}OSC_IN-Pad5)") (class "Default")
      (node (ref "MCU") (pin "5") (pinfunction "PF0/OSC_IN_5") (pintype "bidirectional"))
    )
    (net (code "66") (name "unconnected-(MCU-PF1{slash}OSC_OUT-Pad6)") (class "Default")
      (node (ref "MCU") (pin "6") (pinfunction "PF1/OSC_OUT_6") (pintype "bidirectional"))
    )
    (net (code "67") (name "unconnected-(PI-0_ID_SC-Pad27)") (class "Default")
      (node (ref "PI") (pin "27") (pinfunction "0_ID_SC_27") (pintype "bidirectional"))
    )
    (net (code "68") (name "unconnected-(PI-1_ID_SD-Pad28)") (class "Default")
      (node (ref "PI") (pin "28") (pinfunction "1_ID_SD_28") (pintype "bidirectional"))
    )
    (net (code "69") (name "unconnected-(PI-2-Pad3)") (class "Default")
      (node (ref "PI") (pin "3") (pinfunction "2_3") (pintype "bidirectional"))
    )
    (net (code "70") (name "unconnected-(PI-3-Pad5)") (class "Default")
      (node (ref "PI") (pin "5") (pinfunction "3_5") (pintype "bidirectional"))
    )
    (net (code "71") (name "unconnected-(PI-4-Pad7)") (class "Default")
      (node (ref "PI") (pin "7") (pinfunction "4_7") (pintype "bidirectional"))
    )
    (net (code "72") (name "unconnected-(PI-5-Pad29)") (class "Default")
      (node (ref "PI") (pin "29") (pinfunction "5_29") (pintype "bidirectional"))
    )
    (net (code "73") (name "unconnected-(PI-6-Pad31)") (class "Default")
      (node (ref "PI") (pin "31") (pinfunction "6_31") (pintype "bidirectional"))
    )
    (net (code "74") (name "unconnected-(PI-7-Pad26)") (class "Default")
      (node (ref "PI") (pin "26") (pinfunction "7_26") (pintype "bidirectional"))
    )
    (net (code "75") (name "unconnected-(PI-12-Pad32)") (class "Default")
      (node (ref "PI") (pin "32") (pinfunction "12_32") (pintype "bidirectional"))
    )
    (net (code "76") (name "unconnected-(PI-13-Pad33)") (class "Default")
      (node (ref "PI") (pin "33") (pinfunction "13_33") (pintype "bidirectional"))
    )
    (net (code "77") (name "unconnected-(PI-16-Pad36)") (class "Default")
      (node (ref "PI") (pin "36") (pinfunction "16_36") (pintype "bidirectional"))
    )
    (net (code "78") (name "unconnected-(PI-17-Pad11)") (class "Default")
      (node (ref "PI") (pin "11") (pinfunction "17_11") (pintype "bidirectional"))
    )
    (net (code "79") (name "unconnected-(PI-18-Pad12)") (class "Default")
      (node (ref "PI") (pin "12") (pinfunction "18_12") (pintype "bidirectional"))
    )
    (net (code "80") (name "unconnected-(PI-20-Pad38)") (class "Default")
      (node (ref "PI") (pin "38") (pinfunction "20_38") (pintype "bidirectional"))
    )
    (net (code "81") (name "unconnected-(PI-21-Pad40)") (class "Default")
      (node (ref "PI") (pin "40") (pinfunction "21_40") (pintype "bidirectional"))
    )
    (net (code "82") (name "unconnected-(PI-23-Pad16)") (class "Default")
      (node (ref "PI") (pin "16") (pinfunction "23_16") (pintype "bidirectional"))
    )
    (net (code "83") (name "unconnected-(PI-24-Pad18)") (class "Default")
      (node (ref "PI") (pin "18") (pinfunction "24_18") (pintype "bidirectional"))
    )
    (net (code "84") (name "unconnected-(PI-27-Pad13)") (class "Default")
      (node (ref "PI") (pin "13") (pinfunction "27_13") (pintype "bidirectional"))
    )
    (net (code "85") (name "unconnected-(PI-GND_3-Pad20)") (class "Default")
      (node (ref "PI") (pin "20") (pinfunction "GND_3_20") (pintype "passive"))
    )
    (net (code "86") (name "unconnected-(UC4-NC-PadP5)") (class "Default")
      (node (ref "UC4") (pin "P5") (pinfunction "NC_P5") (pintype "no_connect"))
    )
  )
)
